# Arduino_speed_controller.net
KiCad netlist of a schematic drawn in EAGLE
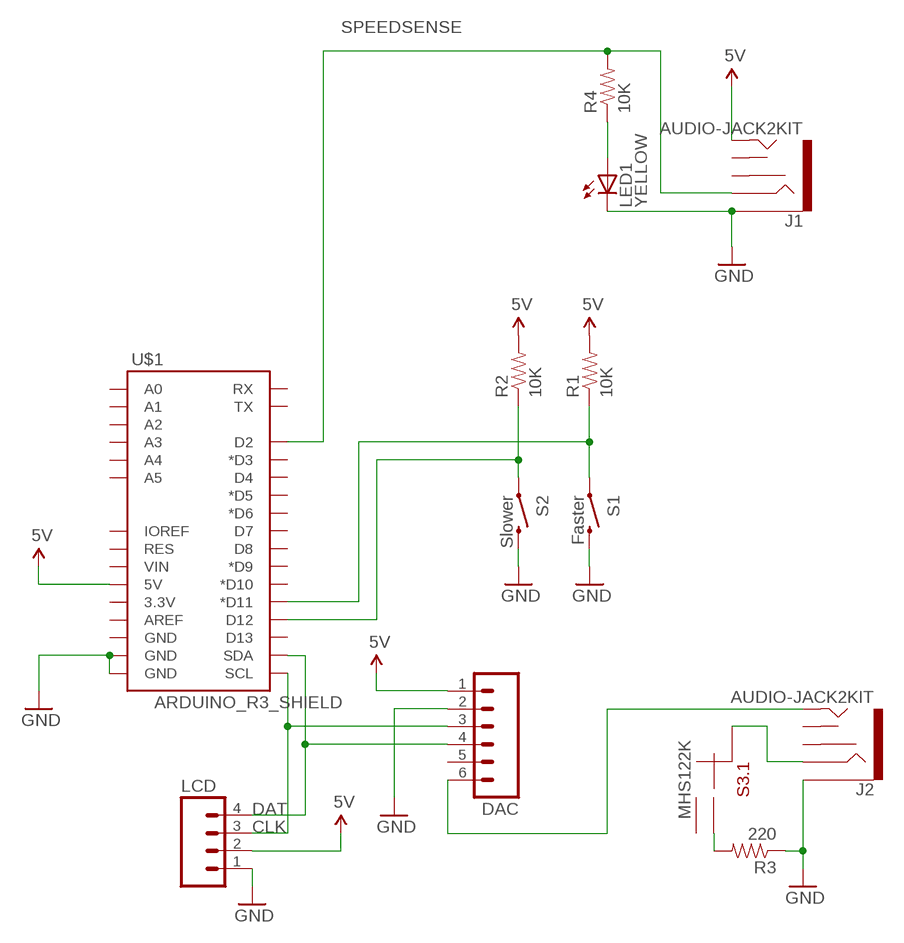
[diagram p0: schematic, sheet 1]

(export (version "E")
  (design (tool "Eeschema 10.0.6"))
  (components
    (comp (ref "DAC")
      (value "M06SIP")
      (footprint "eagle-import:1X06")
      (libsource (lib "eagle-import") (part "M06SIP"))
    )
    (comp (ref "J1")
      (value "AUDIO-JACK2KIT")
      (footprint "eagle-import:AUDIO-JACK-KIT")
      (libsource (lib "eagle-import") (part "AUDIO-JACK2KIT"))
    )
    (comp (ref "J2")
      (value "AUDIO-JACK2KIT")
      (footprint "eagle-import:AUDIO-JACK-KIT")
      (libsource (lib "eagle-import") (part "AUDIO-JACK2KIT"))
    )
    (comp (ref "LCD")
      (value "M04PTH")
      (footprint "eagle-import:1X04")
      (libsource (lib "eagle-import") (part "M04PTH"))
    )
    (comp (ref "LED1")
      (value "YELLOW")
      (footprint "eagle-import:LED3MM")
      (libsource (lib "eagle-import") (part "LED3MM"))
    )
    (comp (ref "R1")
      (value "10K")
      (footprint "eagle-import:AXIAL-0.4")
      (libsource (lib "eagle-import") (part "RESISTORPTH-1/4W"))
    )
    (comp (ref "R2")
      (value "10K")
      (footprint "eagle-import:AXIAL-0.4")
      (libsource (lib "eagle-import") (part "RESISTORPTH-1/4W"))
    )
    (comp (ref "R3")
      (value "220")
      (footprint "eagle-import:AXIAL-0.4")
      (libsource (lib "eagle-import") (part "RESISTORPTH-1/4W"))
    )
    (comp (ref "R4")
      (value "10K")
      (footprint "eagle-import:AXIAL-0.4")
      (libsource (lib "eagle-import") (part "RESISTORPTH-1/4W"))
    )
    (comp (ref "S1")
      (value "Faster")
      (footprint "eagle-import:TACTILE-PTH")
      (libsource (lib "eagle-import") (part "SWITCH-MOMENTARY-2PTH"))
    )
    (comp (ref "S2")
      (value "Slower")
      (footprint "eagle-import:TACTILE-PTH")
      (libsource (lib "eagle-import") (part "SWITCH-MOMENTARY-2PTH"))
    )
    (comp (ref "S3")
      (value "MHS122K")
      (footprint "eagle-import:APEM-MHS122K")
      (libsource (lib "eagle-import") (part "MHS122K"))
    )
    (comp (ref "U$1")
      (value "ARDUINO_R3_SHIELD")
      (footprint "eagle-import:UNO_R3_SHIELD")
      (libsource (lib "eagle-import") (part "ARDUINO_R3_SHIELD"))
    )
  )
  (nets
    (net (code "1") (name "/CLK") (class "Default")
      (node (ref "DAC") (pin "3") (pinfunction "3_3") (pintype "passive"))
      (node (ref "LCD") (pin "3") (pinfunction "3_3") (pintype "passive"))
      (node (ref "U$1") (pin "SCL") (pinfunction "SCL_SCL") (pintype "bidirectional"))
    )
    (net (code "2") (name "/DAT") (class "Default")
      (node (ref "DAC") (pin "4") (pinfunction "4_4") (pintype "passive"))
      (node (ref "LCD") (pin "4") (pinfunction "4_4") (pintype "passive"))
      (node (ref "U$1") (pin "SDA") (pinfunction "SDA_SDA") (pintype "bidirectional"))
    )
    (net (code "3") (name "/SPEEDSENSE") (class "Default")
      (node (ref "J1") (pin "RING") (pinfunction "RING_RING") (pintype "bidirectional"))
      (node (ref "R4") (pin "P$2") (pinfunction "2_P$2") (pintype "passive"))
      (node (ref "U$1") (pin "D2") (pinfunction "D2_D2") (pintype "bidirectional"))
    )
    (net (code "4") (name "5V") (class "Default")
      (node (ref "DAC") (pin "1") (pinfunction "1_1") (pintype "passive"))
      (node (ref "J1") (pin "TIP") (pinfunction "TIP_TIP") (pintype "bidirectional"))
      (node (ref "LCD") (pin "2") (pinfunction "2_2") (pintype "passive"))
      (node (ref "R1") (pin "P$2") (pinfunction "2_P$2") (pintype "passive"))
      (node (ref "R2") (pin "P$2") (pinfunction "2_P$2") (pintype "passive"))
      (node (ref "U$1") (pin "5V") (pinfunction "5V_5V") (pintype "bidirectional"))
    )
    (net (code "5") (name "GND") (class "Default")
      (node (ref "DAC") (pin "2") (pinfunction "2_2") (pintype "passive"))
      (node (ref "J1") (pin "SLEEVE") (pinfunction "SLEEVE_SLEEVE") (pintype "bidirectional"))
      (node (ref "J2") (pin "SLEEVE") (pinfunction "SLEEVE_SLEEVE") (pintype "bidirectional"))
      (node (ref "LCD") (pin "1") (pinfunction "1_1") (pintype "passive"))
      (node (ref "LED1") (pin "K") (pinfunction "C_K") (pintype "passive"))
      (node (ref "R3") (pin "P$1") (pinfunction "1_P$1") (pintype "passive"))
      (node (ref "S1") (pin "3") (pinfunction "2_3") (pintype "passive"))
      (node (ref "S2") (pin "3") (pinfunction "2_3") (pintype "passive"))
      (node (ref "U$1") (pin "GND@0") (pinfunction "GND_GND@0") (pintype "bidirectional"))
      (node (ref "U$1") (pin "GND@1") (pinfunction "GND_GND@1") (pintype "bidirectional"))
    )
    (net (code "6") (name "Net-(DAC-Pad6)") (class "Default")
      (node (ref "DAC") (pin "6") (pinfunction "6_6") (pintype "passive"))
      (node (ref "J2") (pin "TIP") (pinfunction "TIP_TIP") (pintype "bidirectional"))
    )
    (net (code "7") (name "Net-(R1-1)") (class "Default")
      (node (ref "R1") (pin "P$1") (pinfunction "1_P$1") (pintype "passive"))
      (node (ref "S1") (pin "1") (pinfunction "1_1") (pintype "passive"))
      (node (ref "U$1") (pin "D11") (pinfunction "*D11_D11") (pintype "bidirectional"))
    )
    (net (code "8") (name "Net-(R2-1)") (class "Default")
      (node (ref "R2") (pin "P$1") (pinfunction "1_P$1") (pintype "passive"))
      (node (ref "S2") (pin "1") (pinfunction "1_1") (pintype "passive"))
      (node (ref "U$1") (pin "D12") (pinfunction "D12_D12") (pintype "bidirectional"))
    )
    (net (code "9") (name "Net-(R3-2)") (class "Default")
      (node (ref "R3") (pin "P$2") (pinfunction "2_P$2") (pintype "passive"))
      (node (ref "S3") (pin "1") (pinfunction "1_1") (pintype "passive"))
    )
    (net (code "10") (name "Net-(R4-1)") (class "Default")
      (node (ref "LED1") (pin "A") (pinfunction "A_A") (pintype "passive"))
      (node (ref "R4") (pin "P$1") (pinfunction "1_P$1") (pintype "passive"))
    )
    (net (code "11") (name "Net-(S3A-CM)") (class "Default")
      (node (ref "J2") (pin "RING") (pinfunction "RING_RING") (pintype "bidirectional"))
      (node (ref "S3") (pin "CMN") (pinfunction "CM_CMN") (pintype "passive"))
    )
    (net (code "12") (name "unconnected-(DAC-Pad5)") (class "Default")
      (node (ref "DAC") (pin "5") (pinfunction "5_5") (pintype "passive"))
    )
    (net (code "13") (name "unconnected-(J1-PadRSH)") (class "Default")
      (node (ref "J1") (pin "RSH") (pinfunction "RSH_RSH") (pintype "bidirectional"))
    )
    (net (code "14") (name "unconnected-(J1-PadTSH)") (class "Default")
      (node (ref "J1") (pin "TSH") (pinfunction "TSH_TSH") (pintype "bidirectional"))
    )
    (net (code "15") (name "unconnected-(J2-PadRSH)") (class "Default")
      (node (ref "J2") (pin "RSH") (pinfunction "RSH_RSH") (pintype "bidirectional"))
    )
    (net (code "16") (name "unconnected-(J2-PadTSH)") (class "Default")
      (node (ref "J2") (pin "TSH") (pinfunction "TSH_TSH") (pintype "bidirectional"))
    )
    (net (code "17") (name "unconnected-(S3-Pad2)") (class "Default")
      (node (ref "S3") (pin "2") (pinfunction "2_2") (pintype "passive"))
    )
    (net (code "18") (name "unconnected-(U$1-*D3-PadD3)") (class "Default")
      (node (ref "U$1") (pin "D3") (pinfunction "*D3_D3") (pintype "bidirectional"))
    )
    (net (code "19") (name "unconnected-(U$1-*D5-PadD5)") (class "Default")
      (node (ref "U$1") (pin "D5") (pinfunction "*D5_D5") (pintype "bidirectional"))
    )
    (net (code "20") (name "unconnected-(U$1-*D6-PadD6)") (class "Default")
      (node (ref "U$1") (pin "D6") (pinfunction "*D6_D6") (pintype "bidirectional"))
    )
    (net (code "21") (name "unconnected-(U$1-*D9-PadD9)") (class "Default")
      (node (ref "U$1") (pin "D9") (pinfunction "*D9_D9") (pintype "bidirectional"))
    )
    (net (code "22") (name "unconnected-(U$1-*D10-PadD10)") (class "Default")
      (node (ref "U$1") (pin "D10") (pinfunction "*D10_D10") (pintype "bidirectional"))
    )
    (net (code "23") (name "unconnected-(U$1-GND-PadGND@2)") (class "Default")
      (node (ref "U$1") (pin "GND@2") (pinfunction "GND_GND@2") (pintype "bidirectional"))
    )
    (net (code "24") (name "unconnected-(U$1-Pad3.3V)") (class "Default")
      (node (ref "U$1") (pin "3.3V") (pinfunction "3.3V_3.3V") (pintype "bidirectional"))
    )
    (net (code "25") (name "unconnected-(U$1-PadA0)") (class "Default")
      (node (ref "U$1") (pin "A0") (pinfunction "A0_A0") (pintype "bidirectional"))
    )
    (net (code "26") (name "unconnected-(U$1-PadA1)") (class "Default")
      (node (ref "U$1") (pin "A1") (pinfunction "A1_A1") (pintype "bidirectional"))
    )
    (net (code "27") (name "unconnected-(U$1-PadA2)") (class "Default")
      (node (ref "U$1") (pin "A2") (pinfunction "A2_A2") (pintype "bidirectional"))
    )
    (net (code "28") (name "unconnected-(U$1-PadA3)") (class "Default")
      (node (ref "U$1") (pin "A3") (pinfunction "A3_A3") (pintype "bidirectional"))
    )
    (net (code "29") (name "unconnected-(U$1-PadA4)") (class "Default")
      (node (ref "U$1") (pin "A4") (pinfunction "A4_A4") (pintype "bidirectional"))
    )
    (net (code "30") (name "unconnected-(U$1-PadA5)") (class "Default")
      (node (ref "U$1") (pin "A5") (pinfunction "A5_A5") (pintype "bidirectional"))
    )
    (net (code "31") (name "unconnected-(U$1-PadAREF)") (class "Default")
      (node (ref "U$1") (pin "AREF") (pinfunction "AREF_AREF") (pintype "bidirectional"))
    )
    (net (code "32") (name "unconnected-(U$1-PadD4)") (class "Default")
      (node (ref "U$1") (pin "D4") (pinfunction "D4_D4") (pintype "bidirectional"))
    )
    (net (code "33") (name "unconnected-(U$1-PadD7)") (class "Default")
      (node (ref "U$1") (pin "D7") (pinfunction "D7_D7") (pintype "bidirectional"))
    )
    (net (code "34") (name "unconnected-(U$1-PadD8)") (class "Default")
      (node (ref "U$1") (pin "D8") (pinfunction "D8_D8") (pintype "bidirectional"))
    )
    (net (code "35") (name "unconnected-(U$1-PadD13)") (class "Default")
      (node (ref "U$1") (pin "D13") (pinfunction "D13_D13") (pintype "bidirectional"))
    )
    (net (code "36") (name "unconnected-(U$1-PadIOREF)") (class "Default")
      (node (ref "U$1") (pin "IOREF") (pinfunction "IOREF_IOREF") (pintype "bidirectional"))
    )
    (net (code "37") (name "unconnected-(U$1-PadRES)") (class "Default")
      (node (ref "U$1") (pin "RES") (pinfunction "RES_RES") (pintype "bidirectional"))
    )
    (net (code "38") (name "unconnected-(U$1-PadRX)") (class "Default")
      (node (ref "U$1") (pin "RX") (pinfunction "RX_RX") (pintype "bidirectional"))
    )
    (net (code "39") (name "unconnected-(U$1-PadTX)") (class "Default")
      (node (ref "U$1") (pin "TX") (pinfunction "TX_TX") (pintype "bidirectional"))
    )
    (net (code "40") (name "unconnected-(U$1-PadVIN)") (class "Default")
      (node (ref "U$1") (pin "VIN") (pinfunction "VIN_VIN") (pintype "bidirectional"))
    )
  )
)
